# LinearPSURevDV4.net
KiCad netlist of a schematic drawn in EAGLE
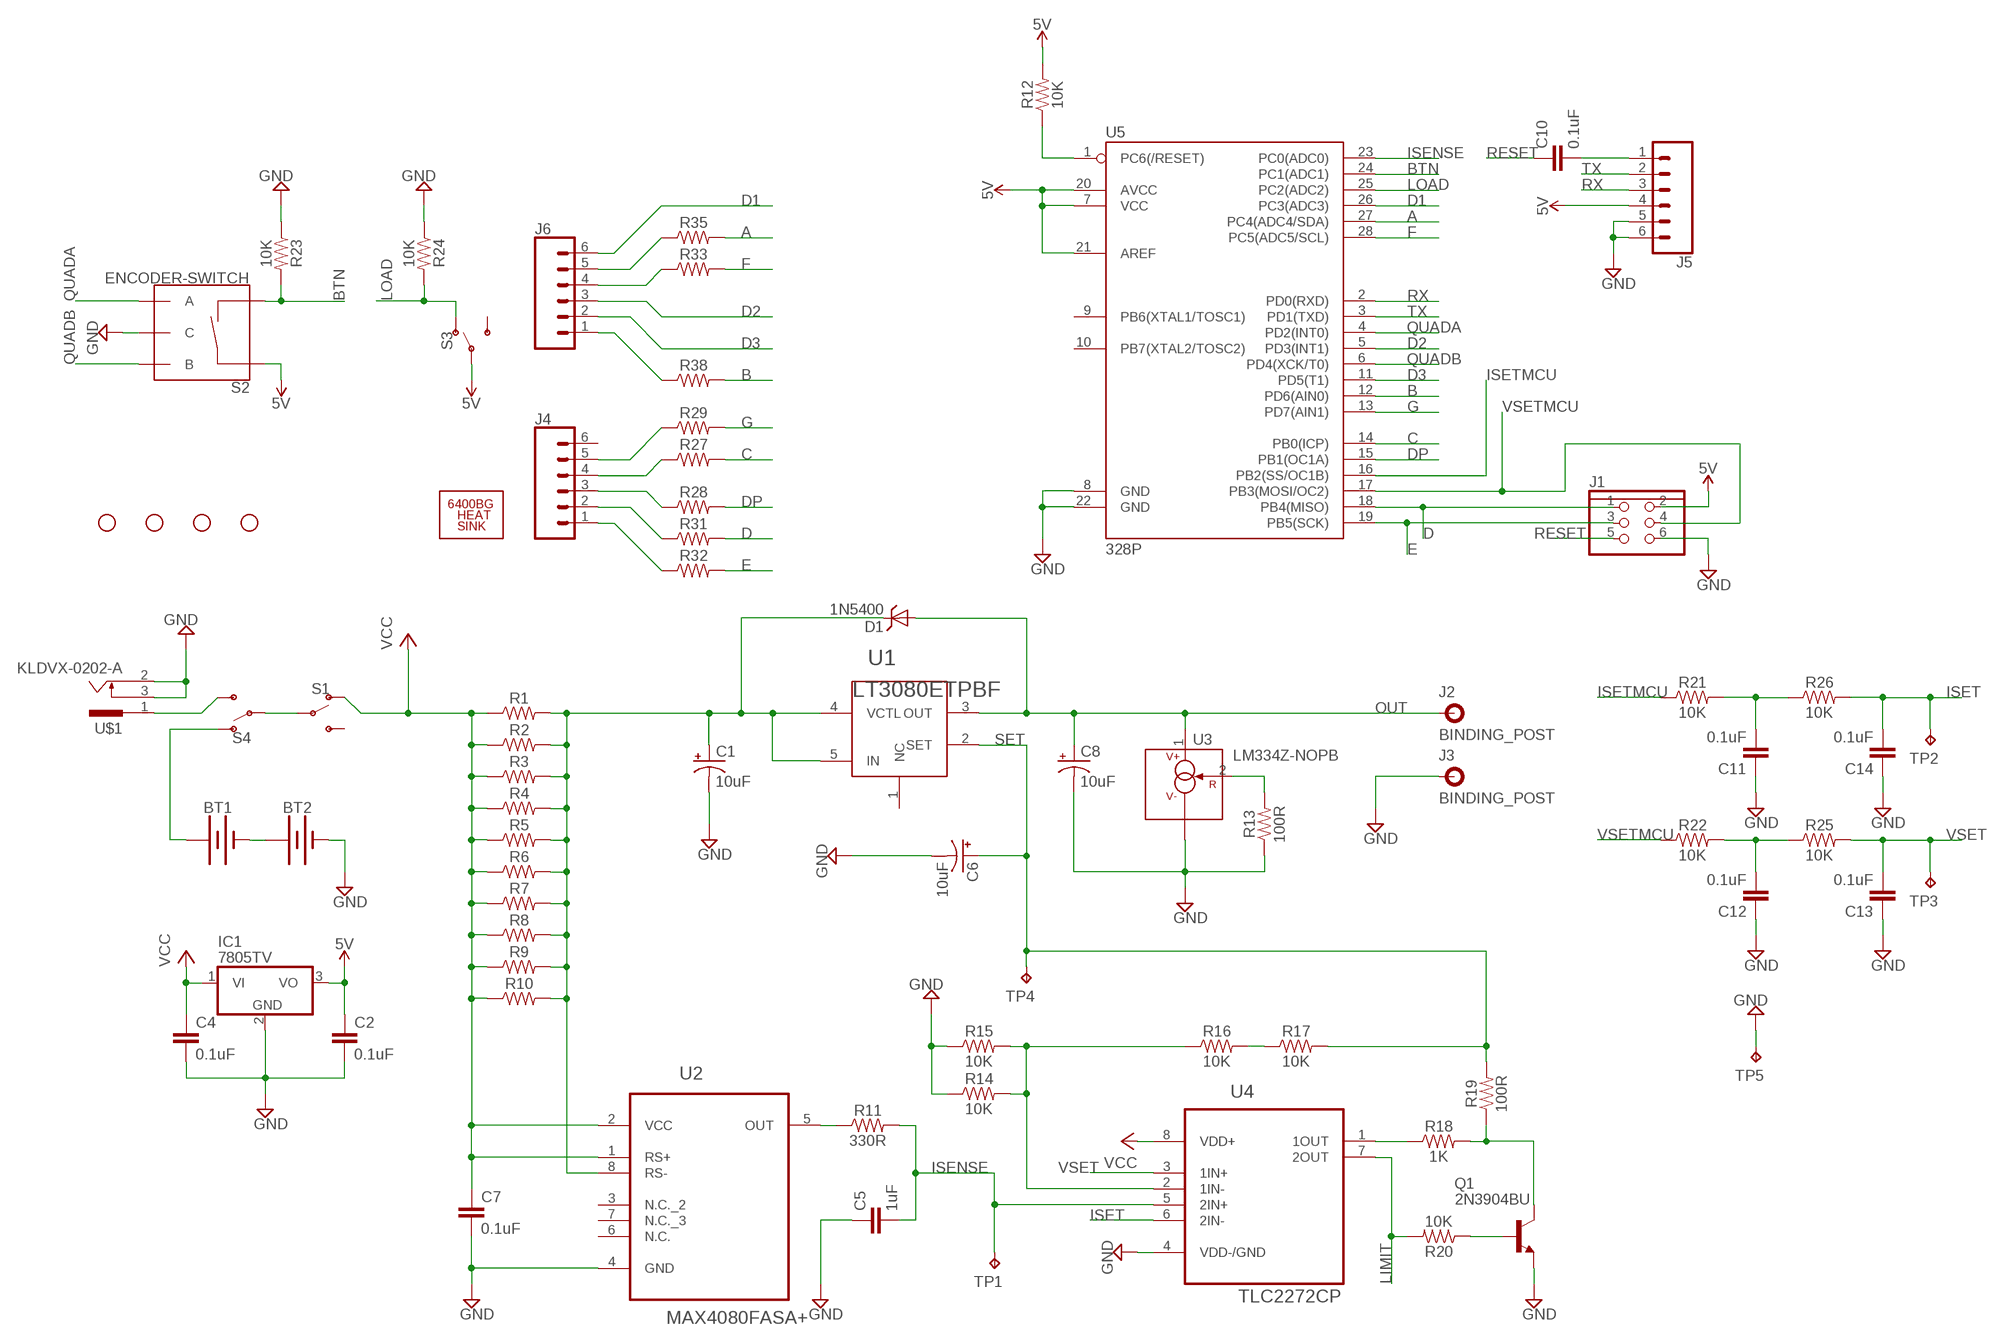
[diagram p0: schematic, sheet 1]

(export (version "E")
  (design (tool "Eeschema 10.0.6"))
  (components
    (comp (ref "BT1")
      (value "BATTERY-9V")
      (footprint "eagle-import:BATTCON_9V")
      (libsource (lib "eagle-import") (part "BATTERY-9V"))
    )
    (comp (ref "BT2")
      (value "BATTERY-9V")
      (footprint "eagle-import:BATTCON_9V")
      (libsource (lib "eagle-import") (part "BATTERY-9V"))
    )
    (comp (ref "C1")
      (value "10uF")
      (footprint "eagle-import:CPOL-RADIAL-2.5MM-5MM")
      (libsource (lib "eagle-import") (part "10UF-POLAR-RADIAL-2.5MM-25V-20%"))
    )
    (comp (ref "C2")
      (value "0.1uF")
      (footprint "eagle-import:CAP-PTH-2.54")
      (libsource (lib "eagle-import") (part "22PF-PTH-2.54MM-200V-5%"))
    )
    (comp (ref "C4")
      (value "0.1uF")
      (footprint "eagle-import:CAP-PTH-2.54")
      (libsource (lib "eagle-import") (part "22PF-PTH-2.54MM-200V-5%"))
    )
    (comp (ref "C5")
      (value "1uF")
      (footprint "eagle-import:CAP-PTH-2.54")
      (libsource (lib "eagle-import") (part "22PF-PTH-2.54MM-200V-5%"))
    )
    (comp (ref "C6")
      (value "10uF")
      (footprint "eagle-import:CPOL-RADIAL-2.5MM-5MM")
      (libsource (lib "eagle-import") (part "10UF-POLAR-RADIAL-2.5MM-25V-20%"))
    )
    (comp (ref "C7")
      (value "0.1uF")
      (footprint "eagle-import:CAP-PTH-2.54")
      (libsource (lib "eagle-import") (part "22PF-PTH-2.54MM-200V-5%"))
    )
    (comp (ref "C8")
      (value "10uF")
      (footprint "eagle-import:CPOL-RADIAL-2.5MM-5MM")
      (libsource (lib "eagle-import") (part "10UF-POLAR-RADIAL-2.5MM-25V-20%"))
    )
    (comp (ref "C10")
      (value "0.1uF")
      (footprint "eagle-import:CAP-PTH-2.54")
      (libsource (lib "eagle-import") (part "22PF-PTH-2.54MM-200V-5%"))
    )
    (comp (ref "C11")
      (value "0.1uF")
      (footprint "eagle-import:CAP-PTH-2.54")
      (libsource (lib "eagle-import") (part "22PF-PTH-2.54MM-200V-5%"))
    )
    (comp (ref "C12")
      (value "0.1uF")
      (footprint "eagle-import:CAP-PTH-2.54")
      (libsource (lib "eagle-import") (part "22PF-PTH-2.54MM-200V-5%"))
    )
    (comp (ref "C13")
      (value "0.1uF")
      (footprint "eagle-import:CAP-PTH-2.54")
      (libsource (lib "eagle-import") (part "22PF-PTH-2.54MM-200V-5%"))
    )
    (comp (ref "C14")
      (value "0.1uF")
      (footprint "eagle-import:CAP-PTH-2.54")
      (libsource (lib "eagle-import") (part "22PF-PTH-2.54MM-200V-5%"))
    )
    (comp (ref "D1")
      (value "1N5400")
      (footprint "eagle-import:DO201-15")
      (fields (field (name "MPN") "1N5400G"))
      (libsource (lib "eagle-import") (part "1N5400"))
    )
    (comp (ref "H1")
      (value "STAND-OFF")
      (footprint "eagle-import:STAND-OFF")
      (libsource (lib "eagle-import") (part "STAND-OFF"))
    )
    (comp (ref "H2")
      (value "STAND-OFF")
      (footprint "eagle-import:STAND-OFF")
      (libsource (lib "eagle-import") (part "STAND-OFF"))
    )
    (comp (ref "H3")
      (value "STAND-OFF")
      (footprint "eagle-import:STAND-OFF")
      (libsource (lib "eagle-import") (part "STAND-OFF"))
    )
    (comp (ref "H4")
      (value "STAND-OFF")
      (footprint "eagle-import:STAND-OFF")
      (libsource (lib "eagle-import") (part "STAND-OFF"))
    )
    (comp (ref "H5")
      (value "6400BG_HEATSINK")
      (footprint "eagle-import:6400BG_HEATSINK")
      (libsource (lib "eagle-import") (part "6400BG_HEATSINK"))
    )
    (comp (ref "IC1")
      (value "7805TV")
      (footprint "eagle-import:TO220V")
      (libsource (lib "eagle-import") (part "78TV05"))
    )
    (comp (ref "J1")
      (value "PINHD2X03")
      (footprint "eagle-import:PINHD2X03")
      (libsource (lib "eagle-import") (part "PINHD2X03"))
    )
    (comp (ref "J2")
      (value "BINDING_POST")
      (footprint "eagle-import:BINDING_POST")
      (libsource (lib "eagle-import") (part "BINDING_POST"))
    )
    (comp (ref "J3")
      (value "BINDING_POST")
      (footprint "eagle-import:BINDING_POST")
      (libsource (lib "eagle-import") (part "BINDING_POST"))
    )
    (comp (ref "J4")
      (value "CONN_06NO_SILK_FEMALE_PTH")
      (footprint "eagle-import:1X06_NO_SILK")
      (libsource (lib "eagle-import") (part "CONN_06NO_SILK_FEMALE_PTH"))
    )
    (comp (ref "J5")
      (value "CONN_06NO_SILK_FEMALE_PTH")
      (footprint "eagle-import:1X06_NO_SILK")
      (libsource (lib "eagle-import") (part "CONN_06NO_SILK_FEMALE_PTH"))
    )
    (comp (ref "J6")
      (value "CONN_06NO_SILK_FEMALE_PTH")
      (footprint "eagle-import:1X06_NO_SILK")
      (libsource (lib "eagle-import") (part "CONN_06NO_SILK_FEMALE_PTH"))
    )
    (comp (ref "Q1")
      (value "2N3904BU")
      (footprint "eagle-import:TO92")
      (libsource (lib "eagle-import") (part "2N3904BU"))
    )
    (comp (ref "R1")
      (value "2R")
      (footprint "eagle-import:0603")
      (libsource (lib "eagle-import") (part "0OHM-0603-1/10W-5%"))
    )
    (comp (ref "R2")
      (value "2R")
      (footprint "eagle-import:0603")
      (libsource (lib "eagle-import") (part "0OHM-0603-1/10W-5%"))
    )
    (comp (ref "R3")
      (value "2R")
      (footprint "eagle-import:0603")
      (libsource (lib "eagle-import") (part "0OHM-0603-1/10W-5%"))
    )
    (comp (ref "R4")
      (value "2R")
      (footprint "eagle-import:0603")
      (libsource (lib "eagle-import") (part "0OHM-0603-1/10W-5%"))
    )
    (comp (ref "R5")
      (value "2R")
      (footprint "eagle-import:0603")
      (libsource (lib "eagle-import") (part "0OHM-0603-1/10W-5%"))
    )
    (comp (ref "R6")
      (value "2R")
      (footprint "eagle-import:0603")
      (libsource (lib "eagle-import") (part "0OHM-0603-1/10W-5%"))
    )
    (comp (ref "R7")
      (value "2R")
      (footprint "eagle-import:0603")
      (libsource (lib "eagle-import") (part "0OHM-0603-1/10W-5%"))
    )
    (comp (ref "R8")
      (value "2R")
      (footprint "eagle-import:0603")
      (libsource (lib "eagle-import") (part "0OHM-0603-1/10W-5%"))
    )
    (comp (ref "R9")
      (value "2R")
      (footprint "eagle-import:0603")
      (libsource (lib "eagle-import") (part "0OHM-0603-1/10W-5%"))
    )
    (comp (ref "R10")
      (value "2R")
      (footprint "eagle-import:0603")
      (libsource (lib "eagle-import") (part "0OHM-0603-1/10W-5%"))
    )
    (comp (ref "R11")
      (value "330R")
      (footprint "eagle-import:AXIAL-0.3")
      (libsource (lib "eagle-import") (part "1KOHM-HORIZ-1/4W-1%"))
    )
    (comp (ref "R12")
      (value "10K")
      (footprint "eagle-import:AXIAL-0.3")
      (libsource (lib "eagle-import") (part "1KOHM-HORIZ-1/4W-1%"))
    )
    (comp (ref "R13")
      (value "100R")
      (footprint "eagle-import:AXIAL-0.3")
      (libsource (lib "eagle-import") (part "1KOHM-HORIZ-1/4W-1%"))
    )
    (comp (ref "R14")
      (value "10K")
      (footprint "eagle-import:AXIAL-0.3")
      (libsource (lib "eagle-import") (part "1KOHM-HORIZ-1/4W-1%"))
    )
    (comp (ref "R15")
      (value "10K")
      (footprint "eagle-import:AXIAL-0.3")
      (libsource (lib "eagle-import") (part "1KOHM-HORIZ-1/4W-1%"))
    )
    (comp (ref "R16")
      (value "10K")
      (footprint "eagle-import:AXIAL-0.3")
      (libsource (lib "eagle-import") (part "1KOHM-HORIZ-1/4W-1%"))
    )
    (comp (ref "R17")
      (value "10K")
      (footprint "eagle-import:AXIAL-0.3")
      (libsource (lib "eagle-import") (part "1KOHM-HORIZ-1/4W-1%"))
    )
    (comp (ref "R18")
      (value "1K")
      (footprint "eagle-import:AXIAL-0.3")
      (libsource (lib "eagle-import") (part "1KOHM-HORIZ-1/4W-1%"))
    )
    (comp (ref "R19")
      (value "100R")
      (footprint "eagle-import:AXIAL-0.3")
      (libsource (lib "eagle-import") (part "1KOHM-HORIZ-1/4W-1%"))
    )
    (comp (ref "R20")
      (value "10K")
      (footprint "eagle-import:AXIAL-0.3")
      (libsource (lib "eagle-import") (part "1KOHM-HORIZ-1/4W-1%"))
    )
    (comp (ref "R21")
      (value "10K")
      (footprint "eagle-import:AXIAL-0.3")
      (libsource (lib "eagle-import") (part "1KOHM-HORIZ-1/4W-1%"))
    )
    (comp (ref "R22")
      (value "10K")
      (footprint "eagle-import:AXIAL-0.3")
      (libsource (lib "eagle-import") (part "1KOHM-HORIZ-1/4W-1%"))
    )
    (comp (ref "R23")
      (value "10K")
      (footprint "eagle-import:AXIAL-0.3")
      (libsource (lib "eagle-import") (part "1KOHM-HORIZ-1/4W-1%"))
    )
    (comp (ref "R24")
      (value "10K")
      (footprint "eagle-import:AXIAL-0.3")
      (libsource (lib "eagle-import") (part "1KOHM-HORIZ-1/4W-1%"))
    )
    (comp (ref "R25")
      (value "10K")
      (footprint "eagle-import:AXIAL-0.3")
      (libsource (lib "eagle-import") (part "1KOHM-HORIZ-1/4W-1%"))
    )
    (comp (ref "R26")
      (value "10K")
      (footprint "eagle-import:AXIAL-0.3")
      (libsource (lib "eagle-import") (part "1KOHM-HORIZ-1/4W-1%"))
    )
    (comp (ref "R27")
      (value "10K")
      (footprint "eagle-import:AXIAL-0.3")
      (libsource (lib "eagle-import") (part "1KOHM-HORIZ-1/4W-1%"))
    )
    (comp (ref "R28")
      (value "10K")
      (footprint "eagle-import:AXIAL-0.3")
      (libsource (lib "eagle-import") (part "1KOHM-HORIZ-1/4W-1%"))
    )
    (comp (ref "R29")
      (value "10K")
      (footprint "eagle-import:AXIAL-0.3")
      (libsource (lib "eagle-import") (part "1KOHM-HORIZ-1/4W-1%"))
    )
    (comp (ref "R31")
      (value "10K")
      (footprint "eagle-import:AXIAL-0.3")
      (libsource (lib "eagle-import") (part "1KOHM-HORIZ-1/4W-1%"))
    )
    (comp (ref "R32")
      (value "10K")
      (footprint "eagle-import:AXIAL-0.3")
      (libsource (lib "eagle-import") (part "1KOHM-HORIZ-1/4W-1%"))
    )
    (comp (ref "R33")
      (value "10K")
      (footprint "eagle-import:AXIAL-0.3")
      (libsource (lib "eagle-import") (part "1KOHM-HORIZ-1/4W-1%"))
    )
    (comp (ref "R35")
      (value "10K")
      (footprint "eagle-import:AXIAL-0.3")
      (libsource (lib "eagle-import") (part "1KOHM-HORIZ-1/4W-1%"))
    )
    (comp (ref "R38")
      (value "10K")
      (footprint "eagle-import:AXIAL-0.3")
      (libsource (lib "eagle-import") (part "1KOHM-HORIZ-1/4W-1%"))
    )
    (comp (ref "S1")
      (value "SWITCH-SPDT-PTH-11.6X4.0MM-LOCK")
      (footprint "eagle-import:SWITCH_SPDT_PTH_11.6X4.0MM_LOCK")
      (libsource (lib "eagle-import") (part "SWITCH-SPDT-PTH-11.6X4.0MM-LOCK"))
    )
    (comp (ref "S2")
      (value "ENCODER-SWITCH")
      (footprint "eagle-import:ROTARY_ENC_PLAIN")
      (libsource (lib "eagle-import") (part "ENCODER-SWITCH"))
    )
    (comp (ref "S3")
      (value "SWITCH-SPDT-PTH-11.6X4.0MM-LOCK")
      (footprint "eagle-import:SWITCH_SPDT_PTH_11.6X4.0MM_LOCK")
      (libsource (lib "eagle-import") (part "SWITCH-SPDT-PTH-11.6X4.0MM-LOCK"))
    )
    (comp (ref "S4")
      (value "SWITCH-SPDT-PTH-11.6X4.0MM-LOCK")
      (footprint "eagle-import:SWITCH_SPDT_PTH_11.6X4.0MM_LOCK")
      (libsource (lib "eagle-import") (part "SWITCH-SPDT-PTH-11.6X4.0MM-LOCK"))
    )
    (comp (ref "TP1")
      (value "TPTP14SQ")
      (footprint "eagle-import:TP14SQ")
      (libsource (lib "eagle-import") (part "TPTP14SQ"))
    )
    (comp (ref "TP2")
      (value "TPTP14SQ")
      (footprint "eagle-import:TP14SQ")
      (libsource (lib "eagle-import") (part "TPTP14SQ"))
    )
    (comp (ref "TP3")
      (value "TPTP14SQ")
      (footprint "eagle-import:TP14SQ")
      (libsource (lib "eagle-import") (part "TPTP14SQ"))
    )
    (comp (ref "TP4")
      (value "TPTP14SQ")
      (footprint "eagle-import:TP14SQ")
      (libsource (lib "eagle-import") (part "TPTP14SQ"))
    )
    (comp (ref "TP5")
      (value "TPTP14SQ")
      (footprint "eagle-import:TP14SQ")
      (libsource (lib "eagle-import") (part "TPTP14SQ"))
    )
    (comp (ref "U$1")
      (value "KLDVX-0202-A")
      (footprint "eagle-import:KLDVX-0202-A")
      (libsource (lib "eagle-import") (part "KLDVX-0202-A"))
    )
    (comp (ref "U1")
      (value "LT3080ETPBF")
      (footprint "eagle-import:TO220-51")
      (fields (field (name "MPN") "LT3080ET#PBF"))
      (libsource (lib "eagle-import") (part "LT3080ETPBF"))
    )
    (comp (ref "U2")
      (value "MAX4080FASA+")
      (footprint "eagle-import:SOIC127P600X175-8N")
      (libsource (lib "eagle-import") (part "MAX4080FASA+"))
    )
    (comp (ref "U3")
      (value "LM334Z-NOPB")
      (footprint "eagle-import:TO92")
      (libsource (lib "eagle-import") (part "LM334Z-NOPB"))
    )
    (comp (ref "U4")
      (value "TLC2272CP")
      (footprint "eagle-import:DIP254P762X508-8")
      (libsource (lib "eagle-import") (part "TLC2272CP"))
    )
    (comp (ref "U5")
      (value "328P")
      (footprint "eagle-import:DIP28")
      (libsource (lib "eagle-import") (part "ATMEGA328P_PDIP"))
    )
  )
  (nets
    (net (code "1") (name "/A") (class "Default")
      (node (ref "R35") (pin "P$2") (pinfunction "2_P$2") (pintype "passive"))
      (node (ref "U5") (pin "27") (pinfunction "PC4(ADC4/SDA)_27") (pintype "bidirectional"))
    )
    (net (code "2") (name "/B") (class "Default")
      (node (ref "R38") (pin "P$2") (pinfunction "2_P$2") (pintype "passive"))
      (node (ref "U5") (pin "12") (pinfunction "PD6(AIN0)_12") (pintype "bidirectional"))
    )
    (net (code "3") (name "/BTN") (class "Default")
      (node (ref "R23") (pin "P$2") (pinfunction "2_P$2") (pintype "passive"))
      (node (ref "S2") (pin "SW-") (pinfunction "SW-_SW-") (pintype "bidirectional"))
      (node (ref "U5") (pin "24") (pinfunction "PC1(ADC1)_24") (pintype "bidirectional"))
    )
    (net (code "4") (name "/C") (class "Default")
      (node (ref "R27") (pin "P$2") (pinfunction "2_P$2") (pintype "passive"))
      (node (ref "U5") (pin "14") (pinfunction "PB0(ICP)_14") (pintype "bidirectional"))
    )
    (net (code "5") (name "/D") (class "Default")
      (node (ref "J1") (pin "1") (pinfunction "1_1") (pintype "passive"))
      (node (ref "R31") (pin "P$2") (pinfunction "2_P$2") (pintype "passive"))
      (node (ref "U5") (pin "18") (pinfunction "PB4(MISO)_18") (pintype "bidirectional"))
    )
    (net (code "6") (name "/D1") (class "Default")
      (node (ref "J6") (pin "6") (pinfunction "6_6") (pintype "passive"))
      (node (ref "U5") (pin "26") (pinfunction "PC3(ADC3)_26") (pintype "bidirectional"))
    )
    (net (code "7") (name "/D2") (class "Default")
      (node (ref "J6") (pin "3") (pinfunction "3_3") (pintype "passive"))
      (node (ref "U5") (pin "5") (pinfunction "PD3(INT1)_5") (pintype "bidirectional"))
    )
    (net (code "8") (name "/D3") (class "Default")
      (node (ref "J6") (pin "2") (pinfunction "2_2") (pintype "passive"))
      (node (ref "U5") (pin "11") (pinfunction "PD5(T1)_11") (pintype "bidirectional"))
    )
    (net (code "9") (name "/DP") (class "Default")
      (node (ref "R28") (pin "P$2") (pinfunction "2_P$2") (pintype "passive"))
      (node (ref "U5") (pin "15") (pinfunction "PB1(OC1A)_15") (pintype "bidirectional"))
    )
    (net (code "10") (name "/E") (class "Default")
      (node (ref "J1") (pin "3") (pinfunction "3_3") (pintype "passive"))
      (node (ref "R32") (pin "P$2") (pinfunction "2_P$2") (pintype "passive"))
      (node (ref "U5") (pin "19") (pinfunction "PB5(SCK)_19") (pintype "bidirectional"))
    )
    (net (code "11") (name "/F") (class "Default")
      (node (ref "R33") (pin "P$2") (pinfunction "2_P$2") (pintype "passive"))
      (node (ref "U5") (pin "28") (pinfunction "PC5(ADC5/SCL)_28") (pintype "bidirectional"))
    )
    (net (code "12") (name "/G") (class "Default")
      (node (ref "R29") (pin "P$2") (pinfunction "2_P$2") (pintype "passive"))
      (node (ref "U5") (pin "13") (pinfunction "PD7(AIN1)_13") (pintype "bidirectional"))
    )
    (net (code "13") (name "/ISENSE") (class "Default")
      (node (ref "C5") (pin "2") (pinfunction "2_2") (pintype "passive"))
      (node (ref "R11") (pin "P$2") (pinfunction "2_P$2") (pintype "passive"))
      (node (ref "TP1") (pin "TP") (pinfunction "TP_TP") (pintype "input"))
      (node (ref "U4") (pin "5") (pinfunction "2IN+_5") (pintype "input"))
      (node (ref "U5") (pin "23") (pinfunction "PC0(ADC0)_23") (pintype "bidirectional"))
    )
    (net (code "14") (name "/ISET") (class "Default")
      (node (ref "C14") (pin "2") (pinfunction "2_2") (pintype "passive"))
      (node (ref "R26") (pin "P$2") (pinfunction "2_P$2") (pintype "passive"))
      (node (ref "TP2") (pin "TP") (pinfunction "TP_TP") (pintype "input"))
      (node (ref "U4") (pin "6") (pinfunction "2IN-_6") (pintype "input"))
    )
    (net (code "15") (name "/ISETMCU") (class "Default")
      (node (ref "R21") (pin "P$1") (pinfunction "1_P$1") (pintype "passive"))
      (node (ref "U5") (pin "16") (pinfunction "PB2(SS/OC1B)_16") (pintype "bidirectional"))
    )
    (net (code "16") (name "/LIMIT") (class "Default")
      (node (ref "R20") (pin "P$2") (pinfunction "2_P$2") (pintype "passive"))
      (node (ref "U4") (pin "7") (pinfunction "2OUT_7") (pintype "output"))
    )
    (net (code "17") (name "/LOAD") (class "Default")
      (node (ref "R24") (pin "P$2") (pinfunction "2_P$2") (pintype "passive"))
      (node (ref "S3") (pin "1") (pinfunction "O_1") (pintype "passive"))
      (node (ref "U5") (pin "25") (pinfunction "PC2(ADC2)_25") (pintype "bidirectional"))
    )
    (net (code "18") (name "/OUT") (class "Default")
      (node (ref "C8") (pin "1") (pinfunction "+_1") (pintype "passive"))
      (node (ref "D1") (pin "A") (pinfunction "A_A") (pintype "passive"))
      (node (ref "J2") (pin "P$1") (pinfunction "P$1_P$1") (pintype "bidirectional"))
      (node (ref "U1") (pin "3") (pinfunction "OUT_3") (pintype "output"))
      (node (ref "U3") (pin "1") (pinfunction "V+_1") (pintype "passive"))
    )
    (net (code "19") (name "/QUADA") (class "Default")
      (node (ref "S2") (pin "A") (pinfunction "A_A") (pintype "bidirectional"))
      (node (ref "U5") (pin "4") (pinfunction "PD2(INT0)_4") (pintype "bidirectional"))
    )
    (net (code "20") (name "/QUADB") (class "Default")
      (node (ref "S2") (pin "B") (pinfunction "B_B") (pintype "bidirectional"))
      (node (ref "U5") (pin "6") (pinfunction "PD4(XCK/T0)_6") (pintype "bidirectional"))
    )
    (net (code "21") (name "/RESET") (class "Default")
      (node (ref "C10") (pin "1") (pinfunction "1_1") (pintype "passive"))
      (node (ref "J1") (pin "5") (pinfunction "5_5") (pintype "passive"))
      (node (ref "R12") (pin "P$1") (pinfunction "1_P$1") (pintype "passive"))
      (node (ref "U5") (pin "1") (pinfunction "PC6(/RESET)_1") (pintype "bidirectional"))
    )
    (net (code "22") (name "/RX") (class "Default")
      (node (ref "J5") (pin "3") (pinfunction "3_3") (pintype "passive"))
      (node (ref "U5") (pin "2") (pinfunction "PD0(RXD)_2") (pintype "bidirectional"))
    )
    (net (code "23") (name "/SET") (class "Default")
      (node (ref "C6") (pin "1") (pinfunction "+_1") (pintype "passive"))
      (node (ref "R17") (pin "P$2") (pinfunction "2_P$2") (pintype "passive"))
      (node (ref "R19") (pin "P$2") (pinfunction "2_P$2") (pintype "passive"))
      (node (ref "TP4") (pin "TP") (pinfunction "TP_TP") (pintype "input"))
      (node (ref "U1") (pin "2") (pinfunction "SET_2") (pintype "input"))
    )
    (net (code "24") (name "/TX") (class "Default")
      (node (ref "J5") (pin "2") (pinfunction "2_2") (pintype "passive"))
      (node (ref "U5") (pin "3") (pinfunction "PD1(TXD)_3") (pintype "bidirectional"))
    )
    (net (code "25") (name "/VSET") (class "Default")
      (node (ref "C13") (pin "2") (pinfunction "2_2") (pintype "passive"))
      (node (ref "R25") (pin "P$2") (pinfunction "2_P$2") (pintype "passive"))
      (node (ref "TP3") (pin "TP") (pinfunction "TP_TP") (pintype "input"))
      (node (ref "U4") (pin "3") (pinfunction "1IN+_3") (pintype "input"))
    )
    (net (code "26") (name "/VSETMCU") (class "Default")
      (node (ref "J1") (pin "4") (pinfunction "4_4") (pintype "passive"))
      (node (ref "R22") (pin "P$1") (pinfunction "1_P$1") (pintype "passive"))
      (node (ref "U5") (pin "17") (pinfunction "PB3(MOSI/OC2)_17") (pintype "bidirectional"))
    )
    (net (code "27") (name "5V") (class "Default")
      (node (ref "C2") (pin "1") (pinfunction "1_1") (pintype "passive"))
      (node (ref "IC1") (pin "3") (pinfunction "VO_3") (pintype "passive"))
      (node (ref "J1") (pin "2") (pinfunction "2_2") (pintype "passive"))
      (node (ref "J5") (pin "4") (pinfunction "4_4") (pintype "passive"))
      (node (ref "R12") (pin "P$2") (pinfunction "2_P$2") (pintype "passive"))
      (node (ref "S2") (pin "SW+") (pinfunction "SW+_SW+") (pintype "bidirectional"))
      (node (ref "S3") (pin "2") (pinfunction "P_2") (pintype "passive"))
      (node (ref "U5") (pin "20") (pinfunction "AVCC_20") (pintype "bidirectional"))
      (node (ref "U5") (pin "21") (pinfunction "AREF_21") (pintype "bidirectional"))
      (node (ref "U5") (pin "7") (pinfunction "VCC_7") (pintype "bidirectional"))
    )
    (net (code "28") (name "GND") (class "Default")
      (node (ref "BT2") (pin "-") (pinfunction "-_-") (pintype "power_in"))
      (node (ref "C1") (pin "2") (pinfunction "-_2") (pintype "passive"))
      (node (ref "C11") (pin "1") (pinfunction "1_1") (pintype "passive"))
      (node (ref "C12") (pin "1") (pinfunction "1_1") (pintype "passive"))
      (node (ref "C13") (pin "1") (pinfunction "1_1") (pintype "passive"))
      (node (ref "C14") (pin "1") (pinfunction "1_1") (pintype "passive"))
      (node (ref "C2") (pin "2") (pinfunction "2_2") (pintype "passive"))
      (node (ref "C4") (pin "2") (pinfunction "2_2") (pintype "passive"))
      (node (ref "C5") (pin "1") (pinfunction "1_1") (pintype "passive"))
      (node (ref "C6") (pin "2") (pinfunction "-_2") (pintype "passive"))
      (node (ref "C7") (pin "2") (pinfunction "2_2") (pintype "passive"))
      (node (ref "C8") (pin "2") (pinfunction "-_2") (pintype "passive"))
      (node (ref "IC1") (pin "2") (pinfunction "GND_2") (pintype "passive"))
      (node (ref "J1") (pin "6") (pinfunction "6_6") (pintype "passive"))
      (node (ref "J3") (pin "P$1") (pinfunction "P$1_P$1") (pintype "bidirectional"))
      (node (ref "J5") (pin "5") (pinfunction "5_5") (pintype "passive"))
      (node (ref "J5") (pin "6") (pinfunction "6_6") (pintype "passive"))
      (node (ref "Q1") (pin "3") (pinfunction "E_3") (pintype "passive"))
      (node (ref "R13") (pin "P$1") (pinfunction "1_P$1") (pintype "passive"))
      (node (ref "R14") (pin "P$1") (pinfunction "1_P$1") (pintype "passive"))
      (node (ref "R15") (pin "P$1") (pinfunction "1_P$1") (pintype "passive"))
      (node (ref "R23") (pin "P$1") (pinfunction "1_P$1") (pintype "passive"))
      (node (ref "R24") (pin "P$1") (pinfunction "1_P$1") (pintype "passive"))
      (node (ref "S2") (pin "C") (pinfunction "C_C") (pintype "bidirectional"))
      (node (ref "TP5") (pin "TP") (pinfunction "TP_TP") (pintype "input"))
      (node (ref "U$1") (pin "2") (pinfunction "2_2") (pintype "passive"))
      (node (ref "U$1") (pin "3") (pinfunction "3_3") (pintype "passive"))
      (node (ref "U2") (pin "4") (pinfunction "GND_4") (pintype "passive"))
      (node (ref "U3") (pin "3") (pinfunction "V-_3") (pintype "passive"))
      (node (ref "U4") (pin "4") (pinfunction "VDD-/GND_4") (pintype "passive"))
      (node (ref "U5") (pin "22") (pinfunction "GND_22") (pintype "bidirectional"))
      (node (ref "U5") (pin "8") (pinfunction "GND_8") (pintype "bidirectional"))
    )
    (net (code "29") (name "Net-(BT1-Pad-)") (class "Default")
      (node (ref "BT1") (pin "-") (pinfunction "-_-") (pintype "power_in"))
      (node (ref "BT2") (pin "+") (pinfunction "+_+") (pintype "power_in"))
    )
    (net (code "30") (name "Net-(C1-+)") (class "Default")
      (node (ref "C1") (pin "1") (pinfunction "+_1") (pintype "passive"))
      (node (ref "D1") (pin "C") (pinfunction "C_C") (pintype "passive"))
      (node (ref "R1") (pin "2") (pinfunction "2_2") (pintype "passive"))
      (node (ref "R10") (pin "2") (pinfunction "2_2") (pintype "passive"))
      (node (ref "R2") (pin "2") (pinfunction "2_2") (pintype "passive"))
      (node (ref "R3") (pin "2") (pinfunction "2_2") (pintype "passive"))
      (node (ref "R4") (pin "2") (pinfunction "2_2") (pintype "passive"))
      (node (ref "R5") (pin "2") (pinfunction "2_2") (pintype "passive"))
      (node (ref "R6") (pin "2") (pinfunction "2_2") (pintype "passive"))
      (node (ref "R7") (pin "2") (pinfunction "2_2") (pintype "passive"))
      (node (ref "R8") (pin "2") (pinfunction "2_2") (pintype "passive"))
      (node (ref "R9") (pin "2") (pinfunction "2_2") (pintype "passive"))
      (node (ref "U1") (pin "4") (pinfunction "VCTL_4") (pintype "input"))
      (node (ref "U1") (pin "5") (pinfunction "IN_5") (pintype "input"))
      (node (ref "U2") (pin "8") (pinfunction "RS-_8") (pintype "input"))
    )
    (net (code "31") (name "Net-(C10-Pad2)") (class "Default")
      (node (ref "C10") (pin "2") (pinfunction "2_2") (pintype "passive"))
      (node (ref "J5") (pin "1") (pinfunction "1_1") (pintype "passive"))
    )
    (net (code "32") (name "Net-(Q1-B)") (class "Default")
      (node (ref "Q1") (pin "2") (pinfunction "B_2") (pintype "passive"))
      (node (ref "R20") (pin "P$1") (pinfunction "1_P$1") (pintype "passive"))
    )
    (net (code "33") (name "Net-(Q1-C)") (class "Default")
      (node (ref "Q1") (pin "1") (pinfunction "C_1") (pintype "passive"))
      (node (ref "R18") (pin "P$2") (pinfunction "2_P$2") (pintype "passive"))
      (node (ref "R19") (pin "P$1") (pinfunction "1_P$1") (pintype "passive"))
    )
    (net (code "34") (name "Net-(R11-1)") (class "Default")
      (node (ref "R11") (pin "P$1") (pinfunction "1_P$1") (pintype "passive"))
      (node (ref "U2") (pin "5") (pinfunction "OUT_5") (pintype "output"))
    )
    (net (code "35") (name "Net-(R13-2)") (class "Default")
      (node (ref "R13") (pin "P$2") (pinfunction "2_P$2") (pintype "passive"))
      (node (ref "U3") (pin "2") (pinfunction "R_2") (pintype "passive"))
    )
    (net (code "36") (name "Net-(R14-2)") (class "Default")
      (node (ref "R14") (pin "P$2") (pinfunction "2_P$2") (pintype "passive"))
      (node (ref "R15") (pin "P$2") (pinfunction "2_P$2") (pintype "passive"))
      (node (ref "R16") (pin "P$1") (pinfunction "1_P$1") (pintype "passive"))
      (node (ref "U4") (pin "2") (pinfunction "1IN-_2") (pintype "input"))
    )
    (net (code "37") (name "Net-(R16-2)") (class "Default")
      (node (ref "R16") (pin "P$2") (pinfunction "2_P$2") (pintype "passive"))
      (node (ref "R17") (pin "P$1") (pinfunction "1_P$1") (pintype "passive"))
    )
    (net (code "38") (name "Net-(R18-1)") (class "Default")
      (node (ref "R18") (pin "P$1") (pinfunction "1_P$1") (pintype "passive"))
      (node (ref "U4") (pin "1") (pinfunction "1OUT_1") (pintype "output"))
    )
    (net (code "39") (name "Net-(R21-2)") (class "Default")
      (node (ref "C11") (pin "2") (pinfunction "2_2") (pintype "passive"))
      (node (ref "R21") (pin "P$2") (pinfunction "2_P$2") (pintype "passive"))
      (node (ref "R26") (pin "P$1") (pinfunction "1_P$1") (pintype "passive"))
    )
    (net (code "40") (name "Net-(R22-2)") (class "Default")
      (node (ref "C12") (pin "2") (pinfunction "2_2") (pintype "passive"))
      (node (ref "R22") (pin "P$2") (pinfunction "2_P$2") (pintype "passive"))
      (node (ref "R25") (pin "P$1") (pinfunction "1_P$1") (pintype "passive"))
    )
    (net (code "41") (name "Net-(R27-1)") (class "Default")
      (node (ref "J4") (pin "4") (pinfunction "4_4") (pintype "passive"))
      (node (ref "R27") (pin "P$1") (pinfunction "1_P$1") (pintype "passive"))
    )
    (net (code "42") (name "Net-(R28-1)") (class "Default")
      (node (ref "J4") (pin "3") (pinfunction "3_3") (pintype "passive"))
      (node (ref "R28") (pin "P$1") (pinfunction "1_P$1") (pintype "passive"))
    )
    (net (code "43") (name "Net-(R29-1)") (class "Default")
      (node (ref "J4") (pin "5") (pinfunction "5_5") (pintype "passive"))
      (node (ref "R29") (pin "P$1") (pinfunction "1_P$1") (pintype "passive"))
    )
    (net (code "44") (name "Net-(R31-1)") (class "Default")
      (node (ref "J4") (pin "2") (pinfunction "2_2") (pintype "passive"))
      (node (ref "R31") (pin "P$1") (pinfunction "1_P$1") (pintype "passive"))
    )
    (net (code "45") (name "Net-(R32-1)") (class "Default")
      (node (ref "J4") (pin "1") (pinfunction "1_1") (pintype "passive"))
      (node (ref "R32") (pin "P$1") (pinfunction "1_P$1") (pintype "passive"))
    )
    (net (code "46") (name "Net-(R33-1)") (class "Default")
      (node (ref "J6") (pin "4") (pinfunction "4_4") (pintype "passive"))
      (node (ref "R33") (pin "P$1") (pinfunction "1_P$1") (pintype "passive"))
    )
    (net (code "47") (name "Net-(R35-1)") (class "Default")
      (node (ref "J6") (pin "5") (pinfunction "5_5") (pintype "passive"))
      (node (ref "R35") (pin "P$1") (pinfunction "1_P$1") (pintype "passive"))
    )
    (net (code "48") (name "Net-(R38-1)") (class "Default")
      (node (ref "J6") (pin "1") (pinfunction "1_1") (pintype "passive"))
      (node (ref "R38") (pin "P$1") (pinfunction "1_P$1") (pintype "passive"))
    )
    (net (code "49") (name "Net-(S1-P)") (class "Default")
      (node (ref "S1") (pin "2") (pinfunction "P_2") (pintype "passive"))
      (node (ref "S4") (pin "2") (pinfunction "P_2") (pintype "passive"))
    )
    (net (code "50") (name "Net-(S4-O)") (class "Default")
      (node (ref "BT1") (pin "+") (pinfunction "+_+") (pintype "power_in"))
      (node (ref "S4") (pin "1") (pinfunction "O_1") (pintype "passive"))
    )
    (net (code "51") (name "Net-(S4-S)") (class "Default")
      (node (ref "S4") (pin "3") (pinfunction "S_3") (pintype "passive"))
      (node (ref "U$1") (pin "1") (pinfunction "1_1") (pintype "passive"))
    )
    (net (code "52") (name "VCC") (class "Default")
      (node (ref "C4") (pin "1") (pinfunction "1_1") (pintype "passive"))
      (node (ref "C7") (pin "1") (pinfunction "1_1") (pintype "passive"))
      (node (ref "IC1") (pin "1") (pinfunction "VI_1") (pintype "input"))
      (node (ref "R1") (pin "1") (pinfunction "1_1") (pintype "passive"))
      (node (ref "R10") (pin "1") (pinfunction "1_1") (pintype "passive"))
      (node (ref "R2") (pin "1") (pinfunction "1_1") (pintype "passive"))
      (node (ref "R3") (pin "1") (pinfunction "1_1") (pintype "passive"))
      (node (ref "R4") (pin "1") (pinfunction "1_1") (pintype "passive"))
      (node (ref "R5") (pin "1") (pinfunction "1_1") (pintype "passive"))
      (node (ref "R6") (pin "1") (pinfunction "1_1") (pintype "passive"))
      (node (ref "R7") (pin "1") (pinfunction "1_1") (pintype "passive"))
      (node (ref "R8") (pin "1") (pinfunction "1_1") (pintype "passive"))
      (node (ref "R9") (pin "1") (pinfunction "1_1") (pintype "passive"))
      (node (ref "S1") (pin "1") (pinfunction "O_1") (pintype "passive"))
      (node (ref "U2") (pin "1") (pinfunction "RS+_1") (pintype "input"))
      (node (ref "U2") (pin "2") (pinfunction "VCC_2") (pintype "power_in"))
      (node (ref "U4") (pin "8") (pinfunction "VDD+_8") (pintype "power_in"))
    )
    (net (code "53") (name "unconnected-(J4-Pad6)") (class "Default")
      (node (ref "J4") (pin "6") (pinfunction "6_6") (pintype "passive"))
    )
    (net (code "54") (name "unconnected-(S1-S-Pad3)") (class "Default")
      (node (ref "S1") (pin "3") (pinfunction "S_3") (pintype "passive"))
    )
    (net (code "55") (name "unconnected-(S3-S-Pad3)") (class "Default")
      (node (ref "S3") (pin "3") (pinfunction "S_3") (pintype "passive"))
    )
    (net (code "56") (name "unconnected-(U$1-1-Pad1@1)") (class "Default")
      (node (ref "U$1") (pin "1@1") (pinfunction "1_1@1") (pintype "passive"))
    )
    (net (code "57") (name "unconnected-(U$1-2-Pad2@1)") (class "Default")
      (node (ref "U$1") (pin "2@1") (pinfunction "2_2@1") (pintype "passive"))
    )
    (net (code "58") (name "unconnected-(U$1-3-Pad3@1)") (class "Default")
      (node (ref "U$1") (pin "3@1") (pinfunction "3_3@1") (pintype "passive"))
    )
    (net (code "59") (name "unconnected-(U1-NC-Pad1)") (class "Default")
      (node (ref "U1") (pin "1") (pinfunction "NC_1") (pintype "bidirectional"))
    )
    (net (code "60") (name "unconnected-(U2-N.C.-Pad6)") (class "Default")
      (node (ref "U2") (pin "6") (pinfunction "N.C._6") (pintype "no_connect"))
    )
    (net (code "61") (name "unconnected-(U2-N.C._2-Pad3)") (class "Default")
      (node (ref "U2") (pin "3") (pinfunction "N.C._2_3") (pintype "no_connect"))
    )
    (net (code "62") (name "unconnected-(U2-N.C._3-Pad7)") (class "Default")
      (node (ref "U2") (pin "7") (pinfunction "N.C._3_7") (pintype "no_connect"))
    )
    (net (code "63") (name "unconnected-(U5-PB6(XTAL1{slash}TOSC1)-Pad9)") (class "Default")
      (node (ref "U5") (pin "9") (pinfunction "PB6(XTAL1/TOSC1)_9") (pintype "bidirectional"))
    )
    (net (code "64") (name "unconnected-(U5-PB7(XTAL2{slash}TOSC2)-Pad10)") (class "Default")
      (node (ref "U5") (pin "10") (pinfunction "PB7(XTAL2/TOSC2)_10") (pintype "bidirectional"))
    )
  )
)
